# hat_v3.net
KiCad netlist of a schematic drawn in EAGLE
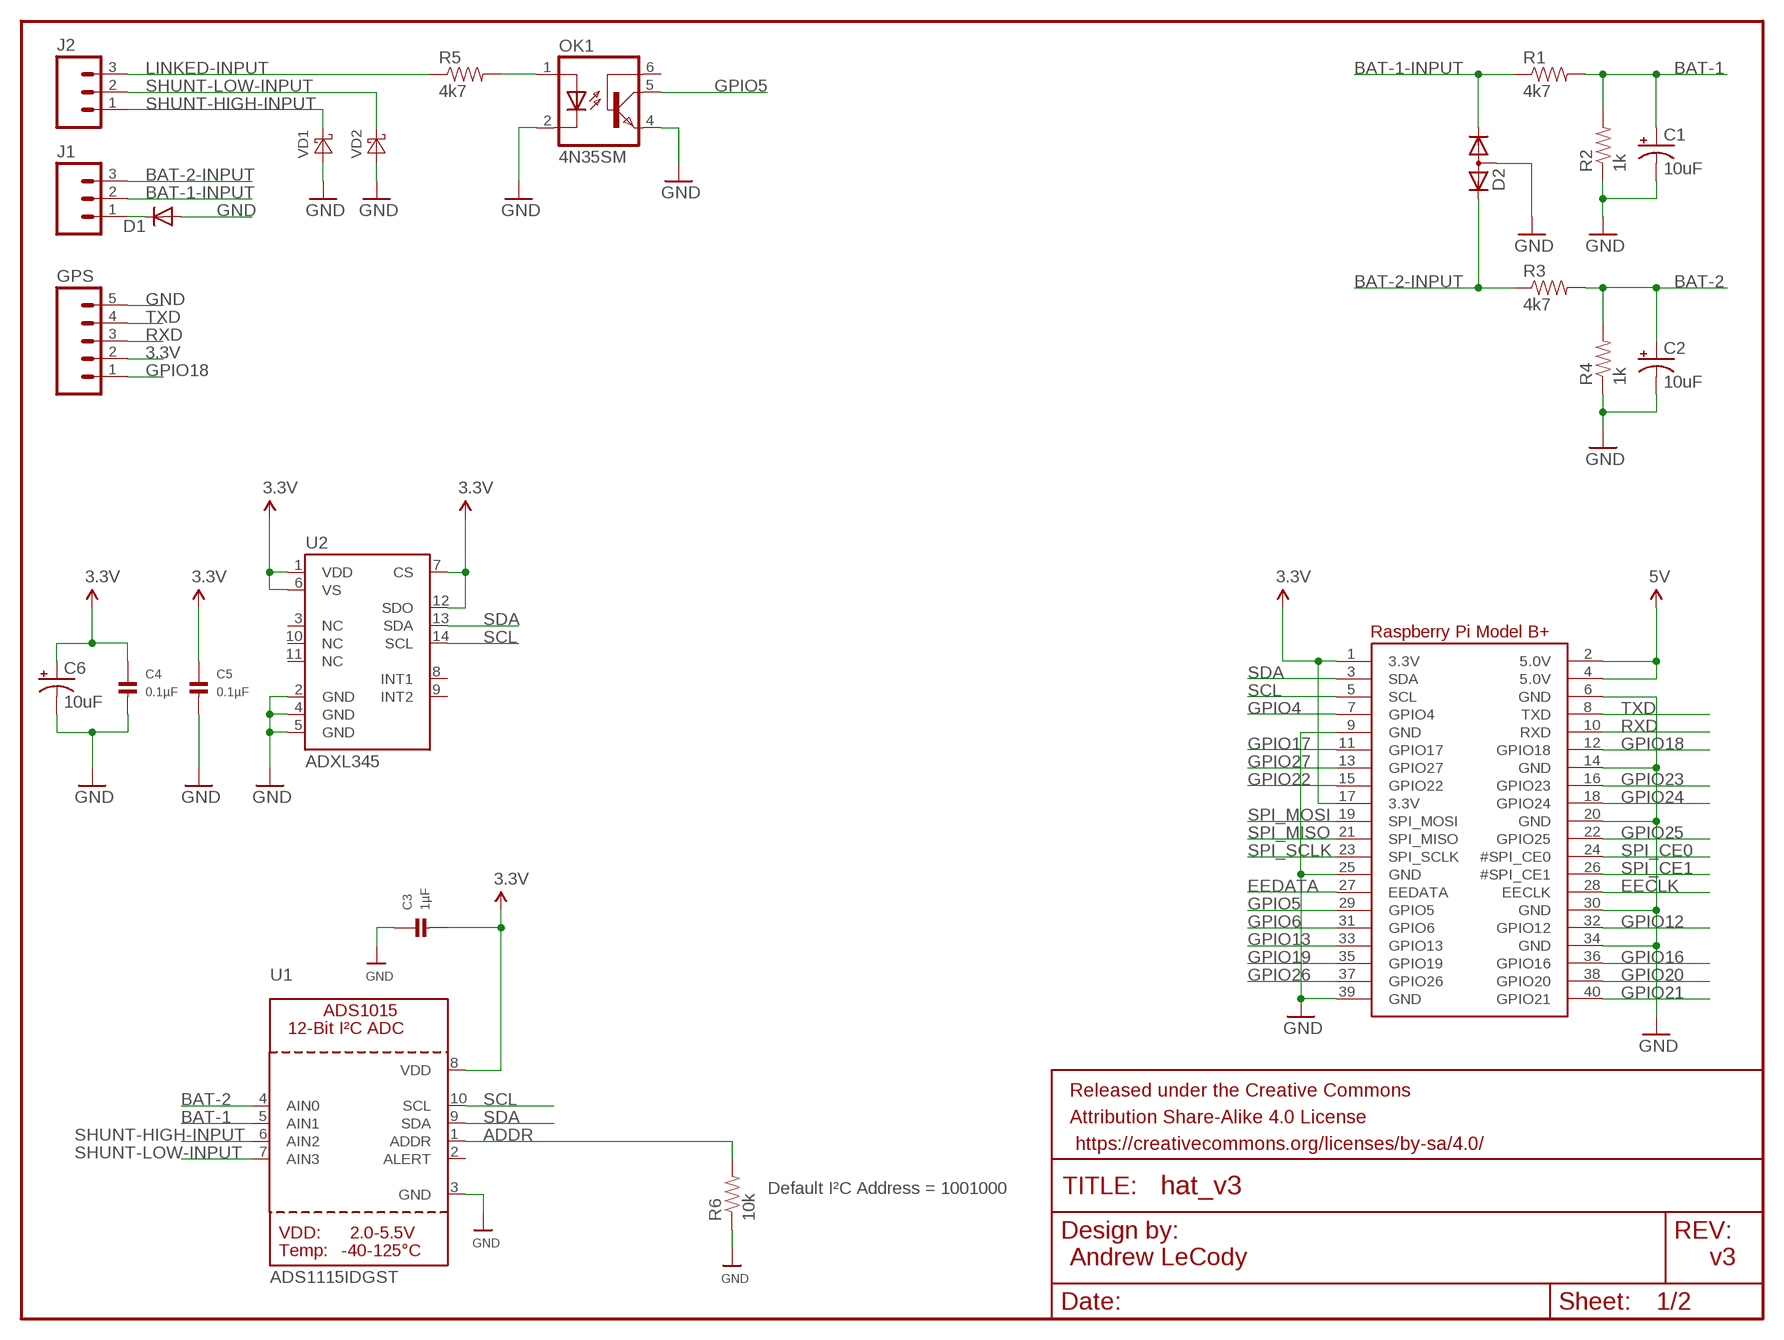
[diagram p0: schematic, sheet 1]
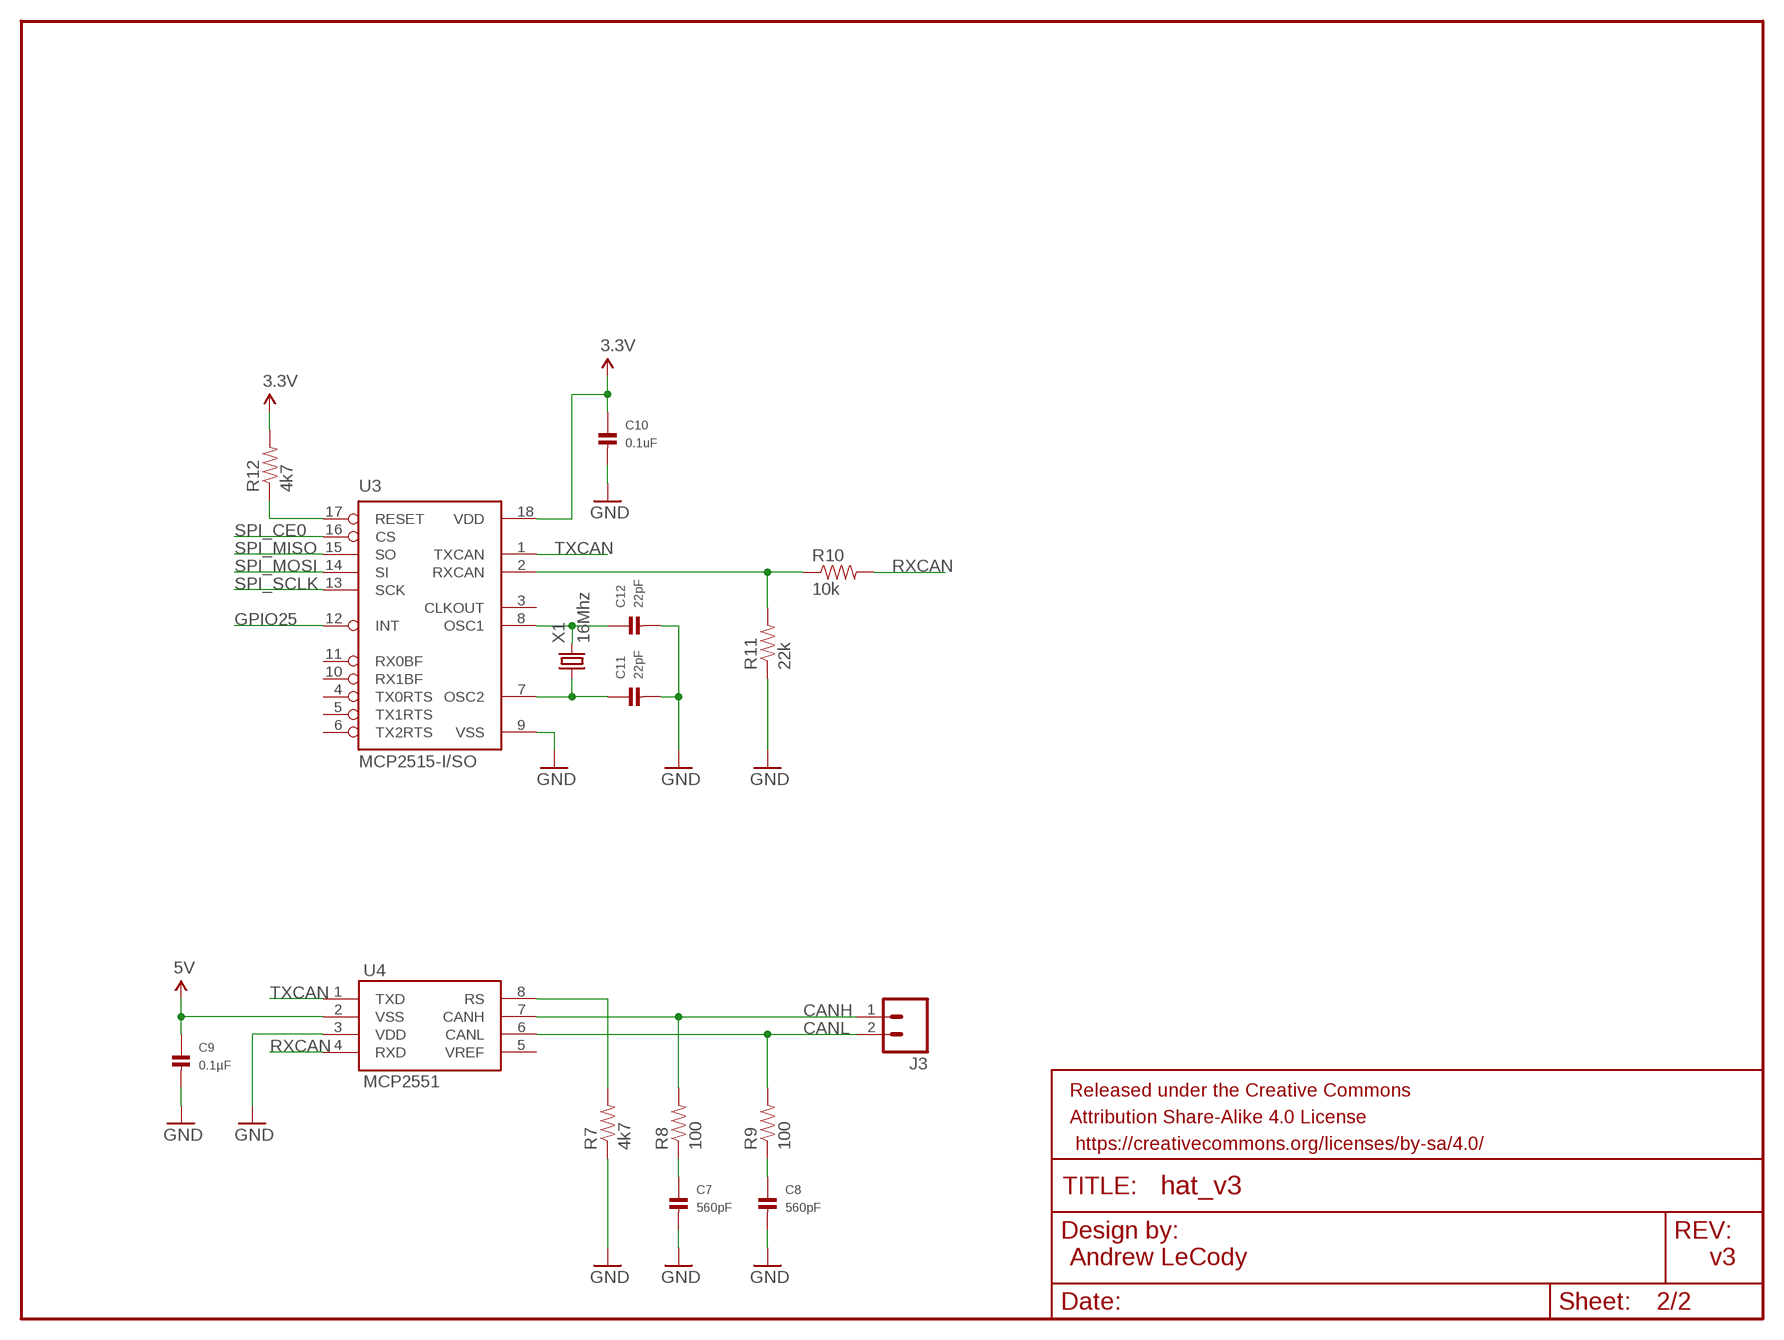
[diagram p1: schematic, sheet 2]

(export (version "E")
  (design (tool "Eeschema 10.0.6"))
  (components
    (comp (ref "C7")
      (value "560pF")
      (footprint "eagle-import:0805")
      (libsource (lib "eagle-import") (part "CAP_CERAMIC0805"))
    )
    (comp (ref "C8")
      (value "560pF")
      (footprint "eagle-import:0805")
      (libsource (lib "eagle-import") (part "CAP_CERAMIC0805"))
    )
    (comp (ref "C9")
      (value "0.1µF")
      (footprint "eagle-import:0805")
      (libsource (lib "eagle-import") (part "CAP_CERAMIC0805"))
    )
    (comp (ref "C10")
      (value "0.1uF")
      (footprint "eagle-import:0805")
      (libsource (lib "eagle-import") (part "CAP_CERAMIC0805"))
    )
    (comp (ref "C11")
      (value "22pF")
      (footprint "eagle-import:0805")
      (libsource (lib "eagle-import") (part "CAP_CERAMIC0805"))
    )
    (comp (ref "C12")
      (value "22pF")
      (footprint "eagle-import:0805")
      (libsource (lib "eagle-import") (part "CAP_CERAMIC0805"))
    )
    (comp (ref "FRAME2")
      (value "FRAME-LETTERNO_PACKAGE")
      (footprint "eagle-import:DUMMY")
      (fields (field (name "DESIGNER") "Nobody"))
      (libsource (lib "eagle-import") (part "FRAME-LETTERNO_PACKAGE"))
    )
    (comp (ref "J3")
      (value "M025MM")
      (footprint "eagle-import:SCREWTERMINAL-5MM-2")
      (libsource (lib "eagle-import") (part "M025MM"))
    )
    (comp (ref "R7")
      (value "4k7")
      (footprint "eagle-import:0805")
      (libsource (lib "eagle-import") (part "RESISTOR0805-RES"))
    )
    (comp (ref "R8")
      (value "100")
      (footprint "eagle-import:0805")
      (libsource (lib "eagle-import") (part "RESISTOR0805-RES"))
    )
    (comp (ref "R9")
      (value "100")
      (footprint "eagle-import:0805")
      (libsource (lib "eagle-import") (part "RESISTOR0805-RES"))
    )
    (comp (ref "R10")
      (value "10k")
      (footprint "eagle-import:0805")
      (libsource (lib "eagle-import") (part "RESISTOR0805-RES"))
    )
    (comp (ref "R11")
      (value "22k")
      (footprint "eagle-import:0805")
      (libsource (lib "eagle-import") (part "RESISTOR0805-RES"))
    )
    (comp (ref "R12")
      (value "4k7")
      (footprint "eagle-import:0805")
      (libsource (lib "eagle-import") (part "RESISTOR0805-RES"))
    )
    (comp (ref "U3")
      (value "MCP2515-I/SO")
      (footprint "eagle-import:SO18L")
      (libsource (lib "eagle-import") (part "MCP2515-I/SO"))
    )
    (comp (ref "U4")
      (value "MCP2551")
      (footprint "eagle-import:SO08")
      (libsource (lib "eagle-import") (part "MCP2551"))
    )
    (comp (ref "X1")
      (value "16Mhz")
      (footprint "eagle-import:HC49-4-HSMX")
      (libsource (lib "eagle-import") (part "CRYSTALS-NOGND-4-HSMX"))
    )
    (comp (ref "C1")
      (value "10uF")
      (footprint "eagle-import:EIA3216")
      (libsource (lib "eagle-import") (part "CAP_POL1206"))
    )
    (comp (ref "C2")
      (value "10uF")
      (footprint "eagle-import:EIA3216")
      (libsource (lib "eagle-import") (part "CAP_POL1206"))
    )
    (comp (ref "C3")
      (value "1µF")
      (footprint "eagle-import:0805")
      (libsource (lib "eagle-import") (part "CAP_CERAMIC0805"))
    )
    (comp (ref "C4")
      (value "0.1µF")
      (footprint "eagle-import:0805")
      (libsource (lib "eagle-import") (part "CAP_CERAMIC0805"))
    )
    (comp (ref "C5")
      (value "0.1µF")
      (footprint "eagle-import:0805")
      (libsource (lib "eagle-import") (part "CAP_CERAMIC0805"))
    )
    (comp (ref "C6")
      (value "10uF")
      (footprint "eagle-import:EIA3216")
      (libsource (lib "eagle-import") (part "CAP_POL1206"))
    )
    (comp (ref "D1")
      (value "DIODE-DO214AC")
      (footprint "eagle-import:DO214AC")
      (libsource (lib "eagle-import") (part "DIODE-DO214AC"))
    )
    (comp (ref "D2")
      (value "DIODE-2CA|ACSOT23")
      (footprint "eagle-import:SOT23")
      (libsource (lib "eagle-import") (part "DIODE-2CA|ACSOT23"))
    )
    (comp (ref "FRAME1")
      (value "FRAME-LETTER")
      (footprint "eagle-import:CREATIVE_COMMONS")
      (libsource (lib "eagle-import") (part "FRAME-LETTER"))
    )
    (comp (ref "GPS")
      (value "M05PTH")
      (footprint "eagle-import:1X05")
      (libsource (lib "eagle-import") (part "M05PTH"))
    )
    (comp (ref "J1")
      (value "M03-SCREW-5MM")
      (footprint "eagle-import:SCREWTERMINAL-5MM-3")
      (libsource (lib "eagle-import") (part "M03-SCREW-5MM"))
    )
    (comp (ref "J2")
      (value "M03-SCREW-5MM")
      (footprint "eagle-import:SCREWTERMINAL-5MM-3")
      (libsource (lib "eagle-import") (part "M03-SCREW-5MM"))
    )
    (comp (ref "OK1")
      (value "4N35SM")
      (footprint "eagle-import:DIL6-SMD")
      (fields (field (name "MF") "FAIRCHILD SEMICONDUCTOR") (field (name "MPN") "4N35S-M"))
      (libsource (lib "eagle-import") (part "4N?MS35"))
    )
    (comp (ref "R1")
      (value "4k7")
      (footprint "eagle-import:0805")
      (libsource (lib "eagle-import") (part "RESISTOR0805-RES"))
    )
    (comp (ref "R2")
      (value "1k")
      (footprint "eagle-import:0805")
      (libsource (lib "eagle-import") (part "RESISTOR0805-RES"))
    )
    (comp (ref "R3")
      (value "4k7")
      (footprint "eagle-import:0805")
      (libsource (lib "eagle-import") (part "RESISTOR0805-RES"))
    )
    (comp (ref "R4")
      (value "1k")
      (footprint "eagle-import:0805")
      (libsource (lib "eagle-import") (part "RESISTOR0805-RES"))
    )
    (comp (ref "R5")
      (value "4k7")
      (footprint "eagle-import:0805")
      (libsource (lib "eagle-import") (part "RESISTOR0805-RES"))
    )
    (comp (ref "R6")
      (value "10k")
      (footprint "eagle-import:0805")
      (libsource (lib "eagle-import") (part "RESISTOR0805-RES"))
    )
    (comp (ref "RPI1")
      (value "RASPBERRYPI_BPLUS_HATNOSLOTS")
      (footprint "eagle-import:PI_HAT_NOSLOTS")
      (libsource (lib "eagle-import") (part "RASPBERRYPI_BPLUS_HATNOSLOTS"))
    )
    (comp (ref "U1")
      (value "ADS1115IDGST")
      (footprint "eagle-import:MSOP10")
      (libsource (lib "eagle-import") (part "ADC_ADS1015"))
    )
    (comp (ref "U2")
      (value "ADXL345")
      (footprint "eagle-import:LGA14")
      (libsource (lib "eagle-import") (part "ADXL345"))
    )
    (comp (ref "VD1")
      (value "DIODE-SCHOTTKY-SOD523")
      (footprint "eagle-import:SOD523")
      (libsource (lib "eagle-import") (part "DIODE-SCHOTTKY-SOD523"))
    )
    (comp (ref "VD2")
      (value "DIODE-SCHOTTKY-SOD523")
      (footprint "eagle-import:SOD523")
      (libsource (lib "eagle-import") (part "DIODE-SCHOTTKY-SOD523"))
    )
  )
  (nets
    (net (code "1") (name "3.3V") (class "Default")
      (node (ref "C10") (pin "1") (pinfunction "P$1_1") (pintype "passive"))
      (node (ref "C3") (pin "2") (pinfunction "P$2_2") (pintype "passive"))
      (node (ref "C4") (pin "1") (pinfunction "P$1_1") (pintype "passive"))
      (node (ref "C5") (pin "1") (pinfunction "P$1_1") (pintype "passive"))
      (node (ref "C6") (pin "A") (pinfunction "+_A") (pintype "passive"))
      (node (ref "GPS") (pin "2") (pinfunction "2_2") (pintype "passive"))
      (node (ref "R12") (pin "2") (pinfunction "2_2") (pintype "passive"))
      (node (ref "RPI1") (pin "1") (pinfunction "3.3V_1") (pintype "power_in"))
      (node (ref "RPI1") (pin "17") (pinfunction "3.3V_17") (pintype "power_in"))
      (node (ref "U1") (pin "8") (pinfunction "VDD_8") (pintype "bidirectional"))
      (node (ref "U2") (pin "1") (pinfunction "VDD_1") (pintype "bidirectional"))
      (node (ref "U2") (pin "12") (pinfunction "SDO_12") (pintype "bidirectional"))
      (node (ref "U2") (pin "6") (pinfunction "VS_6") (pintype "bidirectional"))
      (node (ref "U2") (pin "7") (pinfunction "CS_7") (pintype "bidirectional"))
      (node (ref "U3") (pin "18") (pinfunction "VDD_18") (pintype "power_in"))
    )
    (net (code "2") (name "5V") (class "Default")
      (node (ref "C9") (pin "1") (pinfunction "P$1_1") (pintype "passive"))
      (node (ref "RPI1") (pin "2") (pinfunction "5.0V_2") (pintype "power_in"))
      (node (ref "RPI1") (pin "4") (pinfunction "5.0V_4") (pintype "power_in"))
      (node (ref "U4") (pin "2") (pinfunction "VSS_2") (pintype "bidirectional"))
    )
    (net (code "3") (name "ADDR") (class "Default")
      (node (ref "R6") (pin "2") (pinfunction "2_2") (pintype "passive"))
      (node (ref "U1") (pin "1") (pinfunction "ADDR_1") (pintype "bidirectional"))
    )
    (net (code "4") (name "BAT-1") (class "Default")
      (node (ref "C1") (pin "A") (pinfunction "+_A") (pintype "passive"))
      (node (ref "R1") (pin "2") (pinfunction "2_2") (pintype "passive"))
      (node (ref "R2") (pin "2") (pinfunction "2_2") (pintype "passive"))
      (node (ref "U1") (pin "5") (pinfunction "AIN1_5") (pintype "bidirectional"))
    )
    (net (code "5") (name "BAT-1-INPUT") (class "Default")
      (node (ref "D2") (pin "1") (pinfunction "K1_1") (pintype "passive"))
      (node (ref "J1") (pin "2") (pinfunction "2_2") (pintype "passive"))
      (node (ref "R1") (pin "1") (pinfunction "1_1") (pintype "passive"))
    )
    (net (code "6") (name "BAT-2") (class "Default")
      (node (ref "C2") (pin "A") (pinfunction "+_A") (pintype "passive"))
      (node (ref "R3") (pin "2") (pinfunction "2_2") (pintype "passive"))
      (node (ref "R4") (pin "2") (pinfunction "2_2") (pintype "passive"))
      (node (ref "U1") (pin "4") (pinfunction "AIN0_4") (pintype "bidirectional"))
    )
    (net (code "7") (name "BAT-2-INPUT") (class "Default")
      (node (ref "D2") (pin "2") (pinfunction "K2_2") (pintype "passive"))
      (node (ref "J1") (pin "3") (pinfunction "3_3") (pintype "passive"))
      (node (ref "R3") (pin "1") (pinfunction "1_1") (pintype "passive"))
    )
    (net (code "8") (name "CANH") (class "Default")
      (node (ref "J3") (pin "1") (pinfunction "1_1") (pintype "passive"))
      (node (ref "R8") (pin "2") (pinfunction "2_2") (pintype "passive"))
      (node (ref "U4") (pin "7") (pinfunction "CANH_7") (pintype "bidirectional"))
    )
    (net (code "9") (name "CANL") (class "Default")
      (node (ref "J3") (pin "2") (pinfunction "2_2") (pintype "passive"))
      (node (ref "R9") (pin "2") (pinfunction "2_2") (pintype "passive"))
      (node (ref "U4") (pin "6") (pinfunction "CANL_6") (pintype "bidirectional"))
    )
    (net (code "10") (name "EECLK") (class "Default")
      (node (ref "RPI1") (pin "28") (pinfunction "EECLK_28") (pintype "power_in"))
    )
    (net (code "11") (name "EEDATA") (class "Default")
      (node (ref "RPI1") (pin "27") (pinfunction "EEDATA_27") (pintype "bidirectional"))
    )
    (net (code "12") (name "GND") (class "Default")
      (node (ref "C1") (pin "C") (pinfunction "-_C") (pintype "passive"))
      (node (ref "C10") (pin "2") (pinfunction "P$2_2") (pintype "passive"))
      (node (ref "C11") (pin "2") (pinfunction "P$2_2") (pintype "passive"))
      (node (ref "C12") (pin "2") (pinfunction "P$2_2") (pintype "passive"))
      (node (ref "C2") (pin "C") (pinfunction "-_C") (pintype "passive"))
      (node (ref "C3") (pin "1") (pinfunction "P$1_1") (pintype "passive"))
      (node (ref "C4") (pin "2") (pinfunction "P$2_2") (pintype "passive"))
      (node (ref "C5") (pin "2") (pinfunction "P$2_2") (pintype "passive"))
      (node (ref "C6") (pin "C") (pinfunction "-_C") (pintype "passive"))
      (node (ref "C7") (pin "2") (pinfunction "P$2_2") (pintype "passive"))
      (node (ref "C8") (pin "2") (pinfunction "P$2_2") (pintype "passive"))
      (node (ref "C9") (pin "2") (pinfunction "P$2_2") (pintype "passive"))
      (node (ref "D1") (pin "A") (pinfunction "A_A") (pintype "passive"))
      (node (ref "D2") (pin "3") (pinfunction "A_3") (pintype "passive"))
      (node (ref "GPS") (pin "5") (pinfunction "5_5") (pintype "passive"))
      (node (ref "OK1") (pin "2") (pinfunction "C_2") (pintype "passive"))
      (node (ref "OK1") (pin "4") (pinfunction "EMI_4") (pintype "passive"))
      (node (ref "R11") (pin "1") (pinfunction "1_1") (pintype "passive"))
      (node (ref "R2") (pin "1") (pinfunction "1_1") (pintype "passive"))
      (node (ref "R4") (pin "1") (pinfunction "1_1") (pintype "passive"))
      (node (ref "R6") (pin "1") (pinfunction "1_1") (pintype "passive"))
      (node (ref "R7") (pin "1") (pinfunction "1_1") (pintype "passive"))
      (node (ref "RPI1") (pin "14") (pinfunction "GND_14") (pintype "power_in"))
      (node (ref "RPI1") (pin "20") (pinfunction "GND_20") (pintype "power_in"))
      (node (ref "RPI1") (pin "25") (pinfunction "GND_25") (pintype "power_in"))
      (node (ref "RPI1") (pin "30") (pinfunction "GND_30") (pintype "bidirectional"))
      (node (ref "RPI1") (pin "34") (pinfunction "GND_34") (pintype "bidirectional"))
      (node (ref "RPI1") (pin "39") (pinfunction "GND_39") (pintype "power_in"))
      (node (ref "RPI1") (pin "6") (pinfunction "GND_6") (pintype "power_in"))
      (node (ref "RPI1") (pin "9") (pinfunction "GND_9") (pintype "power_in"))
      (node (ref "U1") (pin "3") (pinfunction "GND_3") (pintype "bidirectional"))
      (node (ref "U2") (pin "2") (pinfunction "GND_2") (pintype "bidirectional"))
      (node (ref "U2") (pin "4") (pinfunction "GND_4") (pintype "bidirectional"))
      (node (ref "U2") (pin "5") (pinfunction "GND_5") (pintype "bidirectional"))
      (node (ref "U3") (pin "9") (pinfunction "VSS_9") (pintype "power_in"))
      (node (ref "U4") (pin "3") (pinfunction "VDD_3") (pintype "bidirectional"))
      (node (ref "VD1") (pin "A") (pinfunction "A_A") (pintype "passive"))
      (node (ref "VD2") (pin "A") (pinfunction "A_A") (pintype "passive"))
    )
    (net (code "13") (name "GPIO4") (class "Default")
      (node (ref "RPI1") (pin "7") (pinfunction "GPIO4_7") (pintype "bidirectional"))
    )
    (net (code "14") (name "GPIO5") (class "Default")
      (node (ref "OK1") (pin "5") (pinfunction "COL_5") (pintype "passive"))
      (node (ref "RPI1") (pin "29") (pinfunction "GPIO5_29") (pintype "bidirectional"))
    )
    (net (code "15") (name "GPIO6") (class "Default")
      (node (ref "RPI1") (pin "31") (pinfunction "GPIO6_31") (pintype "power_in"))
    )
    (net (code "16") (name "GPIO12") (class "Default")
      (node (ref "RPI1") (pin "32") (pinfunction "GPIO12_32") (pintype "bidirectional"))
    )
    (net (code "17") (name "GPIO13") (class "Default")
      (node (ref "RPI1") (pin "33") (pinfunction "GPIO13_33") (pintype "bidirectional"))
    )
    (net (code "18") (name "GPIO16") (class "Default")
      (node (ref "RPI1") (pin "36") (pinfunction "GPIO16_36") (pintype "power_in"))
    )
    (net (code "19") (name "GPIO17") (class "Default")
      (node (ref "RPI1") (pin "11") (pinfunction "GPIO17_11") (pintype "bidirectional"))
    )
    (net (code "20") (name "GPIO18") (class "Default")
      (node (ref "GPS") (pin "1") (pinfunction "1_1") (pintype "passive"))
      (node (ref "RPI1") (pin "12") (pinfunction "GPIO18_12") (pintype "bidirectional"))
    )
    (net (code "21") (name "GPIO19") (class "Default")
      (node (ref "RPI1") (pin "35") (pinfunction "GPIO19_35") (pintype "bidirectional"))
    )
    (net (code "22") (name "GPIO20") (class "Default")
      (node (ref "RPI1") (pin "38") (pinfunction "GPIO20_38") (pintype "bidirectional"))
    )
    (net (code "23") (name "GPIO21") (class "Default")
      (node (ref "RPI1") (pin "40") (pinfunction "GPIO21_40") (pintype "bidirectional"))
    )
    (net (code "24") (name "GPIO22") (class "Default")
      (node (ref "RPI1") (pin "15") (pinfunction "GPIO22_15") (pintype "bidirectional"))
    )
    (net (code "25") (name "GPIO23") (class "Default")
      (node (ref "RPI1") (pin "16") (pinfunction "GPIO23_16") (pintype "bidirectional"))
    )
    (net (code "26") (name "GPIO24") (class "Default")
      (node (ref "RPI1") (pin "18") (pinfunction "GPIO24_18") (pintype "bidirectional"))
    )
    (net (code "27") (name "GPIO25") (class "Default")
      (node (ref "RPI1") (pin "22") (pinfunction "GPIO25_22") (pintype "bidirectional"))
      (node (ref "U3") (pin "12") (pinfunction "INT_12") (pintype "output"))
    )
    (net (code "28") (name "GPIO26") (class "Default")
      (node (ref "RPI1") (pin "37") (pinfunction "GPIO26_37") (pintype "bidirectional"))
    )
    (net (code "29") (name "GPIO27") (class "Default")
      (node (ref "RPI1") (pin "13") (pinfunction "GPIO27_13") (pintype "bidirectional"))
    )
    (net (code "30") (name "LINKED-INPUT") (class "Default")
      (node (ref "J2") (pin "3") (pinfunction "3_3") (pintype "passive"))
      (node (ref "R5") (pin "1") (pinfunction "1_1") (pintype "passive"))
    )
    (net (code "31") (name "Net-(C7-P$1)") (class "Default")
      (node (ref "C7") (pin "1") (pinfunction "P$1_1") (pintype "passive"))
      (node (ref "R8") (pin "1") (pinfunction "1_1") (pintype "passive"))
    )
    (net (code "32") (name "Net-(C8-P$1)") (class "Default")
      (node (ref "C8") (pin "1") (pinfunction "P$1_1") (pintype "passive"))
      (node (ref "R9") (pin "1") (pinfunction "1_1") (pintype "passive"))
    )
    (net (code "33") (name "Net-(C11-P$1)") (class "Default")
      (node (ref "C11") (pin "1") (pinfunction "P$1_1") (pintype "passive"))
      (node (ref "U3") (pin "7") (pinfunction "OSC2_7") (pintype "output"))
      (node (ref "X1") (pin "1") (pinfunction "1_1") (pintype "passive"))
    )
    (net (code "34") (name "Net-(C12-P$1)") (class "Default")
      (node (ref "C12") (pin "1") (pinfunction "P$1_1") (pintype "passive"))
      (node (ref "U3") (pin "8") (pinfunction "OSC1_8") (pintype "input"))
      (node (ref "X1") (pin "2") (pinfunction "2_2") (pintype "passive"))
    )
    (net (code "35") (name "Net-(D1-PadC)") (class "Default")
      (node (ref "D1") (pin "C") (pinfunction "C_C") (pintype "passive"))
      (node (ref "J1") (pin "1") (pinfunction "1_1") (pintype "passive"))
    )
    (net (code "36") (name "Net-(OK1-A)") (class "Default")
      (node (ref "OK1") (pin "1") (pinfunction "A_1") (pintype "passive"))
      (node (ref "R5") (pin "2") (pinfunction "2_2") (pintype "passive"))
    )
    (net (code "37") (name "Net-(U3-RESET)") (class "Default")
      (node (ref "R12") (pin "1") (pinfunction "1_1") (pintype "passive"))
      (node (ref "U3") (pin "17") (pinfunction "RESET_17") (pintype "input"))
    )
    (net (code "38") (name "Net-(U3-RXCAN)") (class "Default")
      (node (ref "R10") (pin "1") (pinfunction "1_1") (pintype "passive"))
      (node (ref "R11") (pin "2") (pinfunction "2_2") (pintype "passive"))
      (node (ref "U3") (pin "2") (pinfunction "RXCAN_2") (pintype "input"))
    )
    (net (code "39") (name "Net-(U4-RS)") (class "Default")
      (node (ref "R7") (pin "2") (pinfunction "2_2") (pintype "passive"))
      (node (ref "U4") (pin "8") (pinfunction "RS_8") (pintype "bidirectional"))
    )
    (net (code "40") (name "RXCAN") (class "Default")
      (node (ref "R10") (pin "2") (pinfunction "2_2") (pintype "passive"))
      (node (ref "U4") (pin "4") (pinfunction "RXD_4") (pintype "bidirectional"))
    )
    (net (code "41") (name "RXD") (class "Default")
      (node (ref "GPS") (pin "3") (pinfunction "3_3") (pintype "passive"))
      (node (ref "RPI1") (pin "10") (pinfunction "RXD_10") (pintype "bidirectional"))
    )
    (net (code "42") (name "SCL") (class "Default")
      (node (ref "RPI1") (pin "5") (pinfunction "SCL_5") (pintype "bidirectional"))
      (node (ref "U1") (pin "10") (pinfunction "SCL_10") (pintype "bidirectional"))
      (node (ref "U2") (pin "14") (pinfunction "SCL_14") (pintype "bidirectional"))
    )
    (net (code "43") (name "SDA") (class "Default")
      (node (ref "RPI1") (pin "3") (pinfunction "SDA_3") (pintype "bidirectional"))
      (node (ref "U1") (pin "9") (pinfunction "SDA_9") (pintype "bidirectional"))
      (node (ref "U2") (pin "13") (pinfunction "SDA_13") (pintype "bidirectional"))
    )
    (net (code "44") (name "SHUNT-HIGH-INPUT") (class "Default")
      (node (ref "J2") (pin "1") (pinfunction "1_1") (pintype "passive"))
      (node (ref "U1") (pin "6") (pinfunction "AIN2_6") (pintype "bidirectional"))
      (node (ref "VD1") (pin "C") (pinfunction "C_C") (pintype "passive"))
    )
    (net (code "45") (name "SHUNT-LOW-INPUT") (class "Default")
      (node (ref "J2") (pin "2") (pinfunction "2_2") (pintype "passive"))
      (node (ref "U1") (pin "7") (pinfunction "AIN3_7") (pintype "bidirectional"))
      (node (ref "VD2") (pin "C") (pinfunction "C_C") (pintype "passive"))
    )
    (net (code "46") (name "SPI_CE0") (class "Default")
      (node (ref "RPI1") (pin "24") (pinfunction "#SPI_CE0_24") (pintype "bidirectional"))
      (node (ref "U3") (pin "16") (pinfunction "CS_16") (pintype "input"))
    )
    (net (code "47") (name "SPI_CE1") (class "Default")
      (node (ref "RPI1") (pin "26") (pinfunction "#SPI_CE1_26") (pintype "bidirectional"))
    )
    (net (code "48") (name "SPI_MISO") (class "Default")
      (node (ref "RPI1") (pin "21") (pinfunction "SPI_MISO_21") (pintype "bidirectional"))
      (node (ref "U3") (pin "15") (pinfunction "SO_15") (pintype "output"))
    )
    (net (code "49") (name "SPI_MOSI") (class "Default")
      (node (ref "RPI1") (pin "19") (pinfunction "SPI_MOSI_19") (pintype "bidirectional"))
      (node (ref "U3") (pin "14") (pinfunction "SI_14") (pintype "input"))
    )
    (net (code "50") (name "SPI_SCLK") (class "Default")
      (node (ref "RPI1") (pin "23") (pinfunction "SPI_SCLK_23") (pintype "bidirectional"))
      (node (ref "U3") (pin "13") (pinfunction "SCK_13") (pintype "input"))
    )
    (net (code "51") (name "TXCAN") (class "Default")
      (node (ref "U3") (pin "1") (pinfunction "TXCAN_1") (pintype "output"))
      (node (ref "U4") (pin "1") (pinfunction "TXD_1") (pintype "bidirectional"))
    )
    (net (code "52") (name "TXD") (class "Default")
      (node (ref "GPS") (pin "4") (pinfunction "4_4") (pintype "passive"))
      (node (ref "RPI1") (pin "8") (pinfunction "TXD_8") (pintype "output"))
    )
    (net (code "53") (name "unconnected-(OK1-BAS-Pad6)") (class "Default")
      (node (ref "OK1") (pin "6") (pinfunction "BAS_6") (pintype "passive"))
    )
    (net (code "54") (name "unconnected-(U1-ALERT-Pad2)") (class "Default")
      (node (ref "U1") (pin "2") (pinfunction "ALERT_2") (pintype "bidirectional"))
    )
    (net (code "55") (name "unconnected-(U2-INT1-Pad8)") (class "Default")
      (node (ref "U2") (pin "8") (pinfunction "INT1_8") (pintype "bidirectional"))
    )
    (net (code "56") (name "unconnected-(U2-INT2-Pad9)") (class "Default")
      (node (ref "U2") (pin "9") (pinfunction "INT2_9") (pintype "bidirectional"))
    )
    (net (code "57") (name "unconnected-(U2-NC-Pad3)") (class "Default")
      (node (ref "U2") (pin "3") (pinfunction "NC_3") (pintype "bidirectional"))
    )
    (net (code "58") (name "unconnected-(U2-NC-Pad10)") (class "Default")
      (node (ref "U2") (pin "10") (pinfunction "NC_10") (pintype "bidirectional"))
    )
    (net (code "59") (name "unconnected-(U2-NC-Pad11)") (class "Default")
      (node (ref "U2") (pin "11") (pinfunction "NC_11") (pintype "bidirectional"))
    )
    (net (code "60") (name "unconnected-(U3-CLKOUT-Pad3)") (class "Default")
      (node (ref "U3") (pin "3") (pinfunction "CLKOUT_3") (pintype "output"))
    )
    (net (code "61") (name "unconnected-(U3-RX0BF-Pad11)") (class "Default")
      (node (ref "U3") (pin "11") (pinfunction "RX0BF_11") (pintype "output"))
    )
    (net (code "62") (name "unconnected-(U3-RX1BF-Pad10)") (class "Default")
      (node (ref "U3") (pin "10") (pinfunction "RX1BF_10") (pintype "output"))
    )
    (net (code "63") (name "unconnected-(U3-TX0RTS-Pad4)") (class "Default")
      (node (ref "U3") (pin "4") (pinfunction "TX0RTS_4") (pintype "input"))
    )
    (net (code "64") (name "unconnected-(U3-TX1RTS-Pad5)") (class "Default")
      (node (ref "U3") (pin "5") (pinfunction "TX1RTS_5") (pintype "input"))
    )
    (net (code "65") (name "unconnected-(U3-TX2RTS-Pad6)") (class "Default")
      (node (ref "U3") (pin "6") (pinfunction "TX2RTS_6") (pintype "input"))
    )
    (net (code "66") (name "unconnected-(U4-VREF-Pad5)") (class "Default")
      (node (ref "U4") (pin "5") (pinfunction "VREF_5") (pintype "bidirectional"))
    )
  )
)
